# transboard.net
KiCad netlist of a schematic drawn in Altium Designer
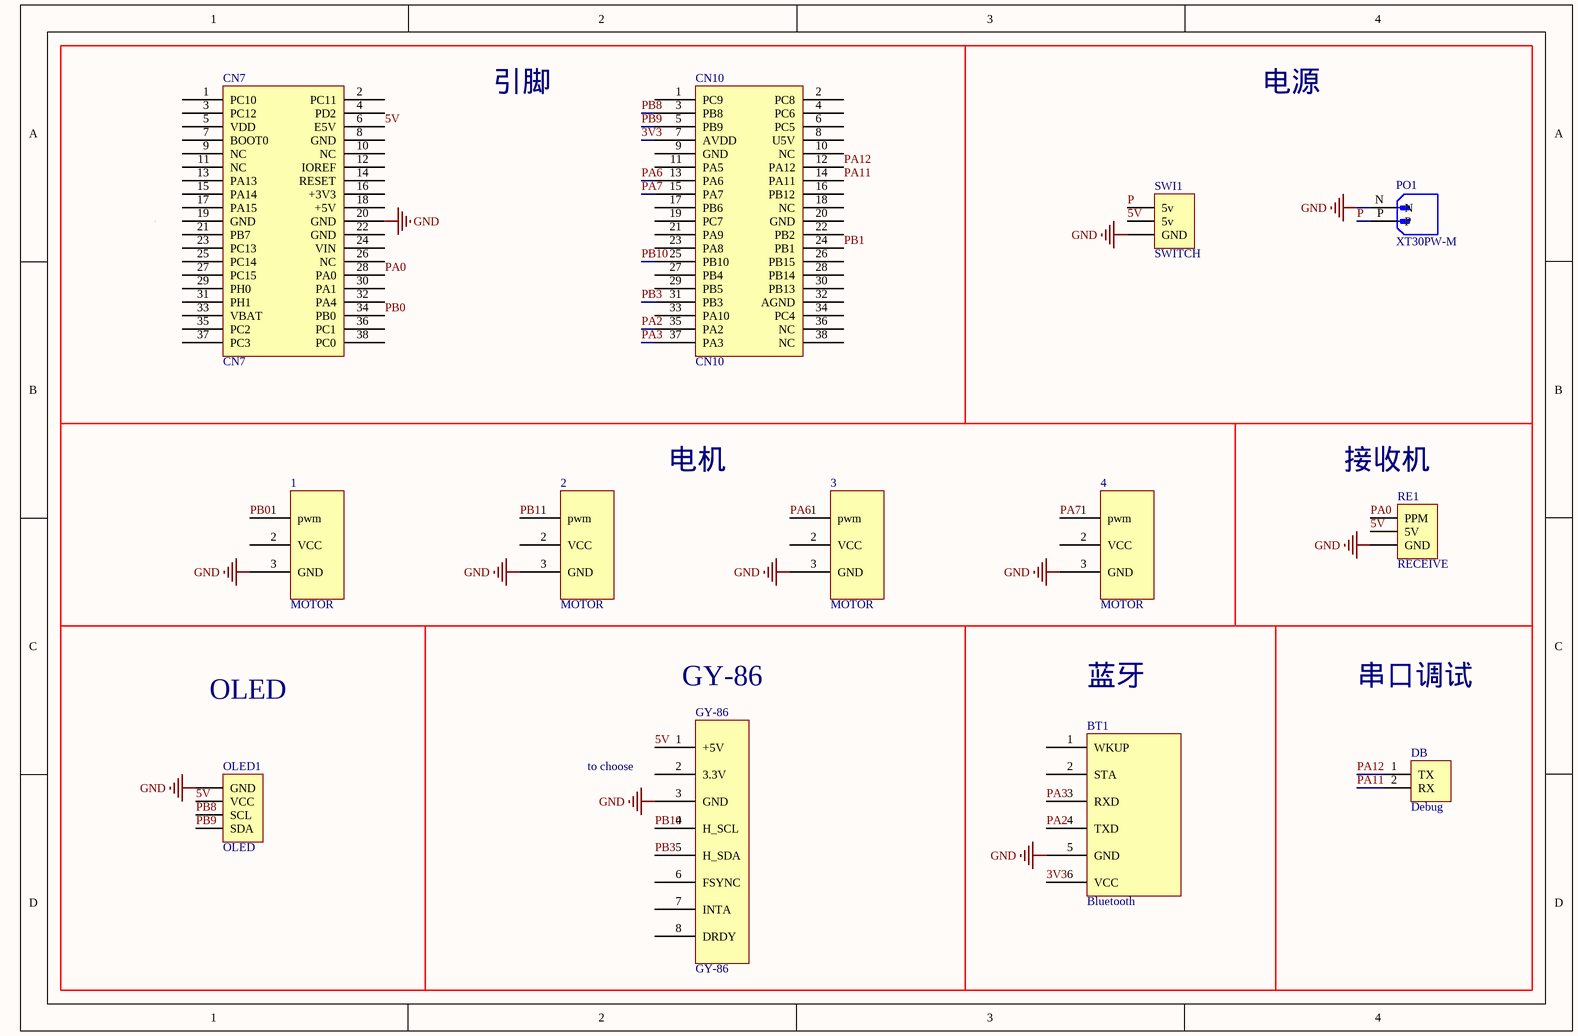
[diagram p0: transboard.SchDoc]

(export (version "E")
  (design (tool "Eeschema 10.0.6"))
  (components
    (comp (ref "1") (value "MOTOR") (footprint "M") (libsource (lib "Free Documents") (part "M")))
    (comp (ref "2") (value "MOTOR") (footprint "M") (libsource (lib "Free Documents") (part "M")))
    (comp (ref "3") (value "MOTOR") (footprint "M") (libsource (lib "Free Documents") (part "M")))
    (comp (ref "4") (value "MOTOR") (footprint "M") (libsource (lib "Free Documents") (part "M")))
    (comp (ref "BT1")
      (value "Bluetooth")
      (footprint "Bluetooth")
      (libsource (lib "Free Documents") (part "Bluetooth"))
    )
    (comp (ref "CN7") (value "CN7") (footprint "CN7") (libsource (lib "Free Documents") (part "CN7")))
    (comp (ref "CN10") (value "CN10") (footprint "CN10") (libsource (lib "Free Documents") (part "CN10")))
    (comp (ref "DB")
      (value "Debug")
      (footprint "HDR1X2")
      (description "Header, 2-Pin")
      (fields (field (name "PUBLISHER") "Altium Limited"))
      (libsource (lib "Miscellaneous Connectors") (part "Header 2"))
    )
    (comp (ref "GY-86") (value "GY-86") (footprint "HDR1X8") (libsource (lib "转接板lib") (part "GY-86")))
    (comp (ref "OLED1")
      (value "OLED")
      (footprint "HDR1X4")
      (description "Header, 4-Pin")
      (fields (field (name "PUBLISHER") "Altium Limited"))
      (libsource (lib "Free Documents") (part "Header 4"))
    )
    (comp (ref "PO1")
      (value "XT30PW-M")
      (footprint "AMASS_XT30PW-M")
      (description "Socket; DC supply; XT30; male; PIN: 2; on PCBs; THT; Colour: yellow")
      (fields (field (name "MF") "AMASS"))
      (libsource (lib "Free Documents") (part "XT30PW-M"))
    )
    (comp (ref "RE1")
      (value "RECEIVE")
      (footprint "HDR1X3")
      (description "Header, 3-Pin")
      (fields (field (name "PUBLISHER") "Altium Limited"))
      (libsource (lib "Free Documents") (part "Header 3"))
    )
    (comp (ref "SWI1")
      (value "SWITCH")
      (footprint "HDR1X3")
      (description "Header, 3-Pin")
      (fields (field (name "PUBLISHER") "Altium Limited"))
      (libsource (lib "Free Documents") (part "Header 3_1"))
    )
  )
  (nets
    (net (code "1") (name "/3V3") (class "Default")
      (node (ref "BT1") (pin "6") (pinfunction "VCC_6") (pintype "passive"))
      (node (ref "CN10") (pin "7") (pinfunction "AVDD_7") (pintype "passive"))
    )
    (net (code "2") (name "/5V") (class "Default")
      (node (ref "CN7") (pin "6") (pinfunction "E5V_6") (pintype "passive"))
      (node (ref "GY-86") (pin "1") (pinfunction "+5V_1") (pintype "passive"))
      (node (ref "OLED1") (pin "2") (pinfunction "VCC_2") (pintype "passive"))
      (node (ref "RE1") (pin "2") (pinfunction "5V_2") (pintype "passive"))
      (node (ref "SWI1") (pin "2") (pinfunction "5v_2") (pintype "passive"))
    )
    (net (code "4") (name "/P") (class "Default")
      (node (ref "PO1") (pin "P") (pinfunction "P_P") (pintype "power_in"))
      (node (ref "SWI1") (pin "1") (pinfunction "5v_1") (pintype "passive"))
    )
    (net (code "5") (name "/PA0") (class "Default")
      (node (ref "CN7") (pin "28") (pinfunction "PA0_28") (pintype "passive"))
      (node (ref "RE1") (pin "1") (pinfunction "PPM_1") (pintype "passive"))
    )
    (net (code "6") (name "/PA2") (class "Default")
      (node (ref "BT1") (pin "4") (pinfunction "TXD_4") (pintype "passive"))
      (node (ref "CN10") (pin "35") (pinfunction "PA2_35") (pintype "passive"))
    )
    (net (code "7") (name "/PA3") (class "Default")
      (node (ref "BT1") (pin "3") (pinfunction "RXD_3") (pintype "passive"))
      (node (ref "CN10") (pin "37") (pinfunction "PA3_37") (pintype "passive"))
    )
    (net (code "8") (name "/PA6") (class "Default")
      (node (ref "3") (pin "1") (pinfunction "pwm_1") (pintype "passive"))
      (node (ref "CN10") (pin "13") (pinfunction "PA6_13") (pintype "passive"))
    )
    (net (code "9") (name "/PA7") (class "Default")
      (node (ref "4") (pin "1") (pinfunction "pwm_1") (pintype "passive"))
      (node (ref "CN10") (pin "15") (pinfunction "PA7_15") (pintype "passive"))
    )
    (net (code "10") (name "/PA11") (class "Default")
      (node (ref "CN10") (pin "14") (pinfunction "PA11_14") (pintype "passive"))
      (node (ref "DB") (pin "2") (pinfunction "RX_2") (pintype "passive"))
    )
    (net (code "11") (name "/PA12") (class "Default")
      (node (ref "CN10") (pin "12") (pinfunction "PA12_12") (pintype "passive"))
      (node (ref "DB") (pin "1") (pinfunction "TX_1") (pintype "passive"))
    )
    (net (code "12") (name "/PB0") (class "Default")
      (node (ref "1") (pin "1") (pinfunction "pwm_1") (pintype "passive"))
      (node (ref "CN7") (pin "34") (pinfunction "PB0_34") (pintype "passive"))
    )
    (net (code "13") (name "/PB1") (class "Default")
      (node (ref "2") (pin "1") (pinfunction "pwm_1") (pintype "passive"))
      (node (ref "CN10") (pin "24") (pinfunction "PB1_24") (pintype "passive"))
    )
    (net (code "14") (name "/PB3") (class "Default")
      (node (ref "CN10") (pin "31") (pinfunction "PB3_31") (pintype "passive"))
      (node (ref "GY-86") (pin "5") (pinfunction "H_SDA_5") (pintype "passive"))
    )
    (net (code "15") (name "/PB8") (class "Default")
      (node (ref "CN10") (pin "3") (pinfunction "PB8_3") (pintype "passive"))
      (node (ref "OLED1") (pin "3") (pinfunction "SCL_3") (pintype "passive"))
    )
    (net (code "16") (name "/PB9") (class "Default")
      (node (ref "CN10") (pin "5") (pinfunction "PB9_5") (pintype "passive"))
      (node (ref "OLED1") (pin "4") (pinfunction "SDA_4") (pintype "passive"))
    )
    (net (code "17") (name "/PB10") (class "Default")
      (node (ref "CN10") (pin "25") (pinfunction "PB10_25") (pintype "passive"))
      (node (ref "GY-86") (pin "4") (pinfunction "H_SCL_4") (pintype "passive"))
    )
    (net (code "18") (name "GND") (class "Default")
      (node (ref "1") (pin "3") (pinfunction "GND_3") (pintype "passive"))
      (node (ref "2") (pin "3") (pinfunction "GND_3") (pintype "passive"))
      (node (ref "3") (pin "3") (pinfunction "GND_3") (pintype "passive"))
      (node (ref "4") (pin "3") (pinfunction "GND_3") (pintype "passive"))
      (node (ref "BT1") (pin "5") (pinfunction "GND_5") (pintype "passive"))
      (node (ref "CN7") (pin "20") (pinfunction "GND_20") (pintype "passive"))
      (node (ref "GY-86") (pin "3") (pinfunction "GND_3") (pintype "passive"))
      (node (ref "OLED1") (pin "1") (pinfunction "GND_1") (pintype "passive"))
      (node (ref "PO1") (pin "N") (pinfunction "N_N") (pintype "power_in"))
      (node (ref "RE1") (pin "3") (pinfunction "GND_3") (pintype "passive"))
      (node (ref "SWI1") (pin "3") (pinfunction "GND_3") (pintype "passive"))
    )
    (net (code "19") (name "unconnected-(1-VCC-Pad2)") (class "Default")
      (node (ref "1") (pin "2") (pinfunction "VCC_2") (pintype "passive"))
    )
    (net (code "20") (name "unconnected-(2-VCC-Pad2)") (class "Default")
      (node (ref "2") (pin "2") (pinfunction "VCC_2") (pintype "passive"))
    )
    (net (code "21") (name "unconnected-(3-VCC-Pad2)") (class "Default")
      (node (ref "3") (pin "2") (pinfunction "VCC_2") (pintype "passive"))
    )
    (net (code "22") (name "unconnected-(4-VCC-Pad2)") (class "Default")
      (node (ref "4") (pin "2") (pinfunction "VCC_2") (pintype "passive"))
    )
    (net (code "23") (name "unconnected-(BT1-STA-Pad2)") (class "Default")
      (node (ref "BT1") (pin "2") (pinfunction "STA_2") (pintype "passive"))
    )
    (net (code "24") (name "unconnected-(BT1-WKUP-Pad1)") (class "Default")
      (node (ref "BT1") (pin "1") (pinfunction "WKUP_1") (pintype "passive"))
    )
    (net (code "25") (name "unconnected-(CN7-+3V3-Pad16)") (class "Default")
      (node (ref "CN7") (pin "16") (pinfunction "+3V3_16") (pintype "passive"))
    )
    (net (code "26") (name "unconnected-(CN7-+5V-Pad18)") (class "Default")
      (node (ref "CN7") (pin "18") (pinfunction "+5V_18") (pintype "passive"))
    )
    (net (code "27") (name "unconnected-(CN7-BOOT0-Pad7)") (class "Default")
      (node (ref "CN7") (pin "7") (pinfunction "BOOT0_7") (pintype "passive"))
    )
    (net (code "28") (name "unconnected-(CN7-GND-Pad8)") (class "Default")
      (node (ref "CN7") (pin "8") (pinfunction "GND_8") (pintype "passive"))
    )
    (net (code "29") (name "unconnected-(CN7-GND-Pad19)") (class "Default")
      (node (ref "CN7") (pin "19") (pinfunction "GND_19") (pintype "passive"))
    )
    (net (code "30") (name "unconnected-(CN7-GND-Pad22)") (class "Default")
      (node (ref "CN7") (pin "22") (pinfunction "GND_22") (pintype "passive"))
    )
    (net (code "31") (name "unconnected-(CN7-IOREF-Pad12)") (class "Default")
      (node (ref "CN7") (pin "12") (pinfunction "IOREF_12") (pintype "passive"))
    )
    (net (code "32") (name "unconnected-(CN7-NC-Pad9)") (class "Default")
      (node (ref "CN7") (pin "9") (pinfunction "NC_9") (pintype "passive"))
    )
    (net (code "33") (name "unconnected-(CN7-NC-Pad10)") (class "Default")
      (node (ref "CN7") (pin "10") (pinfunction "NC_10") (pintype "passive"))
    )
    (net (code "34") (name "unconnected-(CN7-NC-Pad11)") (class "Default")
      (node (ref "CN7") (pin "11") (pinfunction "NC_11") (pintype "passive"))
    )
    (net (code "35") (name "unconnected-(CN7-NC-Pad26)") (class "Default")
      (node (ref "CN7") (pin "26") (pinfunction "NC_26") (pintype "passive"))
    )
    (net (code "36") (name "unconnected-(CN7-PA1-Pad30)") (class "Default")
      (node (ref "CN7") (pin "30") (pinfunction "PA1_30") (pintype "passive"))
    )
    (net (code "37") (name "unconnected-(CN7-PA4-Pad32)") (class "Default")
      (node (ref "CN7") (pin "32") (pinfunction "PA4_32") (pintype "passive"))
    )
    (net (code "38") (name "unconnected-(CN7-PA13-Pad13)") (class "Default")
      (node (ref "CN7") (pin "13") (pinfunction "PA13_13") (pintype "passive"))
    )
    (net (code "39") (name "unconnected-(CN7-PA14-Pad15)") (class "Default")
      (node (ref "CN7") (pin "15") (pinfunction "PA14_15") (pintype "passive"))
    )
    (net (code "40") (name "unconnected-(CN7-PA15-Pad17)") (class "Default")
      (node (ref "CN7") (pin "17") (pinfunction "PA15_17") (pintype "passive"))
    )
    (net (code "41") (name "unconnected-(CN7-PB7-Pad21)") (class "Default")
      (node (ref "CN7") (pin "21") (pinfunction "PB7_21") (pintype "passive"))
    )
    (net (code "42") (name "unconnected-(CN7-PC0-Pad38)") (class "Default")
      (node (ref "CN7") (pin "38") (pinfunction "PC0_38") (pintype "passive"))
    )
    (net (code "43") (name "unconnected-(CN7-PC1-Pad36)") (class "Default")
      (node (ref "CN7") (pin "36") (pinfunction "PC1_36") (pintype "passive"))
    )
    (net (code "44") (name "unconnected-(CN7-PC2-Pad35)") (class "Default")
      (node (ref "CN7") (pin "35") (pinfunction "PC2_35") (pintype "passive"))
    )
    (net (code "45") (name "unconnected-(CN7-PC3-Pad37)") (class "Default")
      (node (ref "CN7") (pin "37") (pinfunction "PC3_37") (pintype "passive"))
    )
    (net (code "46") (name "unconnected-(CN7-PC10-Pad1)") (class "Default")
      (node (ref "CN7") (pin "1") (pinfunction "PC10_1") (pintype "passive"))
    )
    (net (code "47") (name "unconnected-(CN7-PC11-Pad2)") (class "Default")
      (node (ref "CN7") (pin "2") (pinfunction "PC11_2") (pintype "passive"))
    )
    (net (code "48") (name "unconnected-(CN7-PC12-Pad3)") (class "Default")
      (node (ref "CN7") (pin "3") (pinfunction "PC12_3") (pintype "passive"))
    )
    (net (code "49") (name "unconnected-(CN7-PC13-Pad23)") (class "Default")
      (node (ref "CN7") (pin "23") (pinfunction "PC13_23") (pintype "passive"))
    )
    (net (code "50") (name "unconnected-(CN7-PC14-Pad25)") (class "Default")
      (node (ref "CN7") (pin "25") (pinfunction "PC14_25") (pintype "passive"))
    )
    (net (code "51") (name "unconnected-(CN7-PC15-Pad27)") (class "Default")
      (node (ref "CN7") (pin "27") (pinfunction "PC15_27") (pintype "passive"))
    )
    (net (code "52") (name "unconnected-(CN7-PD2-Pad4)") (class "Default")
      (node (ref "CN7") (pin "4") (pinfunction "PD2_4") (pintype "passive"))
    )
    (net (code "53") (name "unconnected-(CN7-PH0-Pad29)") (class "Default")
      (node (ref "CN7") (pin "29") (pinfunction "PH0_29") (pintype "passive"))
    )
    (net (code "54") (name "unconnected-(CN7-PH1-Pad31)") (class "Default")
      (node (ref "CN7") (pin "31") (pinfunction "PH1_31") (pintype "passive"))
    )
    (net (code "55") (name "unconnected-(CN7-RESET-Pad14)") (class "Default")
      (node (ref "CN7") (pin "14") (pinfunction "RESET_14") (pintype "passive"))
    )
    (net (code "56") (name "unconnected-(CN7-VBAT-Pad33)") (class "Default")
      (node (ref "CN7") (pin "33") (pinfunction "VBAT_33") (pintype "passive"))
    )
    (net (code "57") (name "unconnected-(CN7-VDD-Pad5)") (class "Default")
      (node (ref "CN7") (pin "5") (pinfunction "VDD_5") (pintype "passive"))
    )
    (net (code "58") (name "unconnected-(CN7-VIN-Pad24)") (class "Default")
      (node (ref "CN7") (pin "24") (pinfunction "VIN_24") (pintype "passive"))
    )
    (net (code "59") (name "unconnected-(CN10-AGND-Pad32)") (class "Default")
      (node (ref "CN10") (pin "32") (pinfunction "AGND_32") (pintype "passive"))
    )
    (net (code "60") (name "unconnected-(CN10-GND-Pad9)") (class "Default")
      (node (ref "CN10") (pin "9") (pinfunction "GND_9") (pintype "passive"))
    )
    (net (code "61") (name "unconnected-(CN10-GND-Pad20)") (class "Default")
      (node (ref "CN10") (pin "20") (pinfunction "GND_20") (pintype "passive"))
    )
    (net (code "62") (name "unconnected-(CN10-NC-Pad10)") (class "Default")
      (node (ref "CN10") (pin "10") (pinfunction "NC_10") (pintype "passive"))
    )
    (net (code "63") (name "unconnected-(CN10-NC-Pad18)") (class "Default")
      (node (ref "CN10") (pin "18") (pinfunction "NC_18") (pintype "passive"))
    )
    (net (code "64") (name "unconnected-(CN10-NC-Pad36)") (class "Default")
      (node (ref "CN10") (pin "36") (pinfunction "NC_36") (pintype "passive"))
    )
    (net (code "65") (name "unconnected-(CN10-NC-Pad38)") (class "Default")
      (node (ref "CN10") (pin "38") (pinfunction "NC_38") (pintype "passive"))
    )
    (net (code "66") (name "unconnected-(CN10-PA5-Pad11)") (class "Default")
      (node (ref "CN10") (pin "11") (pinfunction "PA5_11") (pintype "passive"))
    )
    (net (code "67") (name "unconnected-(CN10-PA8-Pad23)") (class "Default")
      (node (ref "CN10") (pin "23") (pinfunction "PA8_23") (pintype "passive"))
    )
    (net (code "68") (name "unconnected-(CN10-PA9-Pad21)") (class "Default")
      (node (ref "CN10") (pin "21") (pinfunction "PA9_21") (pintype "passive"))
    )
    (net (code "69") (name "unconnected-(CN10-PA10-Pad33)") (class "Default")
      (node (ref "CN10") (pin "33") (pinfunction "PA10_33") (pintype "passive"))
    )
    (net (code "70") (name "unconnected-(CN10-PB2-Pad22)") (class "Default")
      (node (ref "CN10") (pin "22") (pinfunction "PB2_22") (pintype "passive"))
    )
    (net (code "71") (name "unconnected-(CN10-PB4-Pad27)") (class "Default")
      (node (ref "CN10") (pin "27") (pinfunction "PB4_27") (pintype "passive"))
    )
    (net (code "72") (name "unconnected-(CN10-PB5-Pad29)") (class "Default")
      (node (ref "CN10") (pin "29") (pinfunction "PB5_29") (pintype "passive"))
    )
    (net (code "73") (name "unconnected-(CN10-PB6-Pad17)") (class "Default")
      (node (ref "CN10") (pin "17") (pinfunction "PB6_17") (pintype "passive"))
    )
    (net (code "74") (name "unconnected-(CN10-PB12-Pad16)") (class "Default")
      (node (ref "CN10") (pin "16") (pinfunction "PB12_16") (pintype "passive"))
    )
    (net (code "75") (name "unconnected-(CN10-PB13-Pad30)") (class "Default")
      (node (ref "CN10") (pin "30") (pinfunction "PB13_30") (pintype "passive"))
    )
    (net (code "76") (name "unconnected-(CN10-PB14-Pad28)") (class "Default")
      (node (ref "CN10") (pin "28") (pinfunction "PB14_28") (pintype "passive"))
    )
    (net (code "77") (name "unconnected-(CN10-PB15-Pad26)") (class "Default")
      (node (ref "CN10") (pin "26") (pinfunction "PB15_26") (pintype "passive"))
    )
    (net (code "78") (name "unconnected-(CN10-PC4-Pad34)") (class "Default")
      (node (ref "CN10") (pin "34") (pinfunction "PC4_34") (pintype "passive"))
    )
    (net (code "79") (name "unconnected-(CN10-PC5-Pad6)") (class "Default")
      (node (ref "CN10") (pin "6") (pinfunction "PC5_6") (pintype "passive"))
    )
    (net (code "80") (name "unconnected-(CN10-PC6-Pad4)") (class "Default")
      (node (ref "CN10") (pin "4") (pinfunction "PC6_4") (pintype "passive"))
    )
    (net (code "81") (name "unconnected-(CN10-PC7-Pad19)") (class "Default")
      (node (ref "CN10") (pin "19") (pinfunction "PC7_19") (pintype "passive"))
    )
    (net (code "82") (name "unconnected-(CN10-PC8-Pad2)") (class "Default")
      (node (ref "CN10") (pin "2") (pinfunction "PC8_2") (pintype "passive"))
    )
    (net (code "83") (name "unconnected-(CN10-PC9-Pad1)") (class "Default")
      (node (ref "CN10") (pin "1") (pinfunction "PC9_1") (pintype "passive"))
    )
    (net (code "84") (name "unconnected-(CN10-U5V-Pad8)") (class "Default")
      (node (ref "CN10") (pin "8") (pinfunction "U5V_8") (pintype "passive"))
    )
    (net (code "85") (name "unconnected-(GY-86-3.3V-Pad2)") (class "Default")
      (node (ref "GY-86") (pin "2") (pinfunction "3.3V_2") (pintype "passive"))
    )
    (net (code "86") (name "unconnected-(GY-86-DRDY-Pad8)") (class "Default")
      (node (ref "GY-86") (pin "8") (pinfunction "DRDY_8") (pintype "passive"))
    )
    (net (code "87") (name "unconnected-(GY-86-FSYNC-Pad6)") (class "Default")
      (node (ref "GY-86") (pin "6") (pinfunction "FSYNC_6") (pintype "passive"))
    )
    (net (code "88") (name "unconnected-(GY-86-INTA-Pad7)") (class "Default")
      (node (ref "GY-86") (pin "7") (pinfunction "INTA_7") (pintype "passive"))
    )
  )
)
